# projet_pcb_naked_g431.net
KiCad netlist of a schematic drawn in Altium Designer
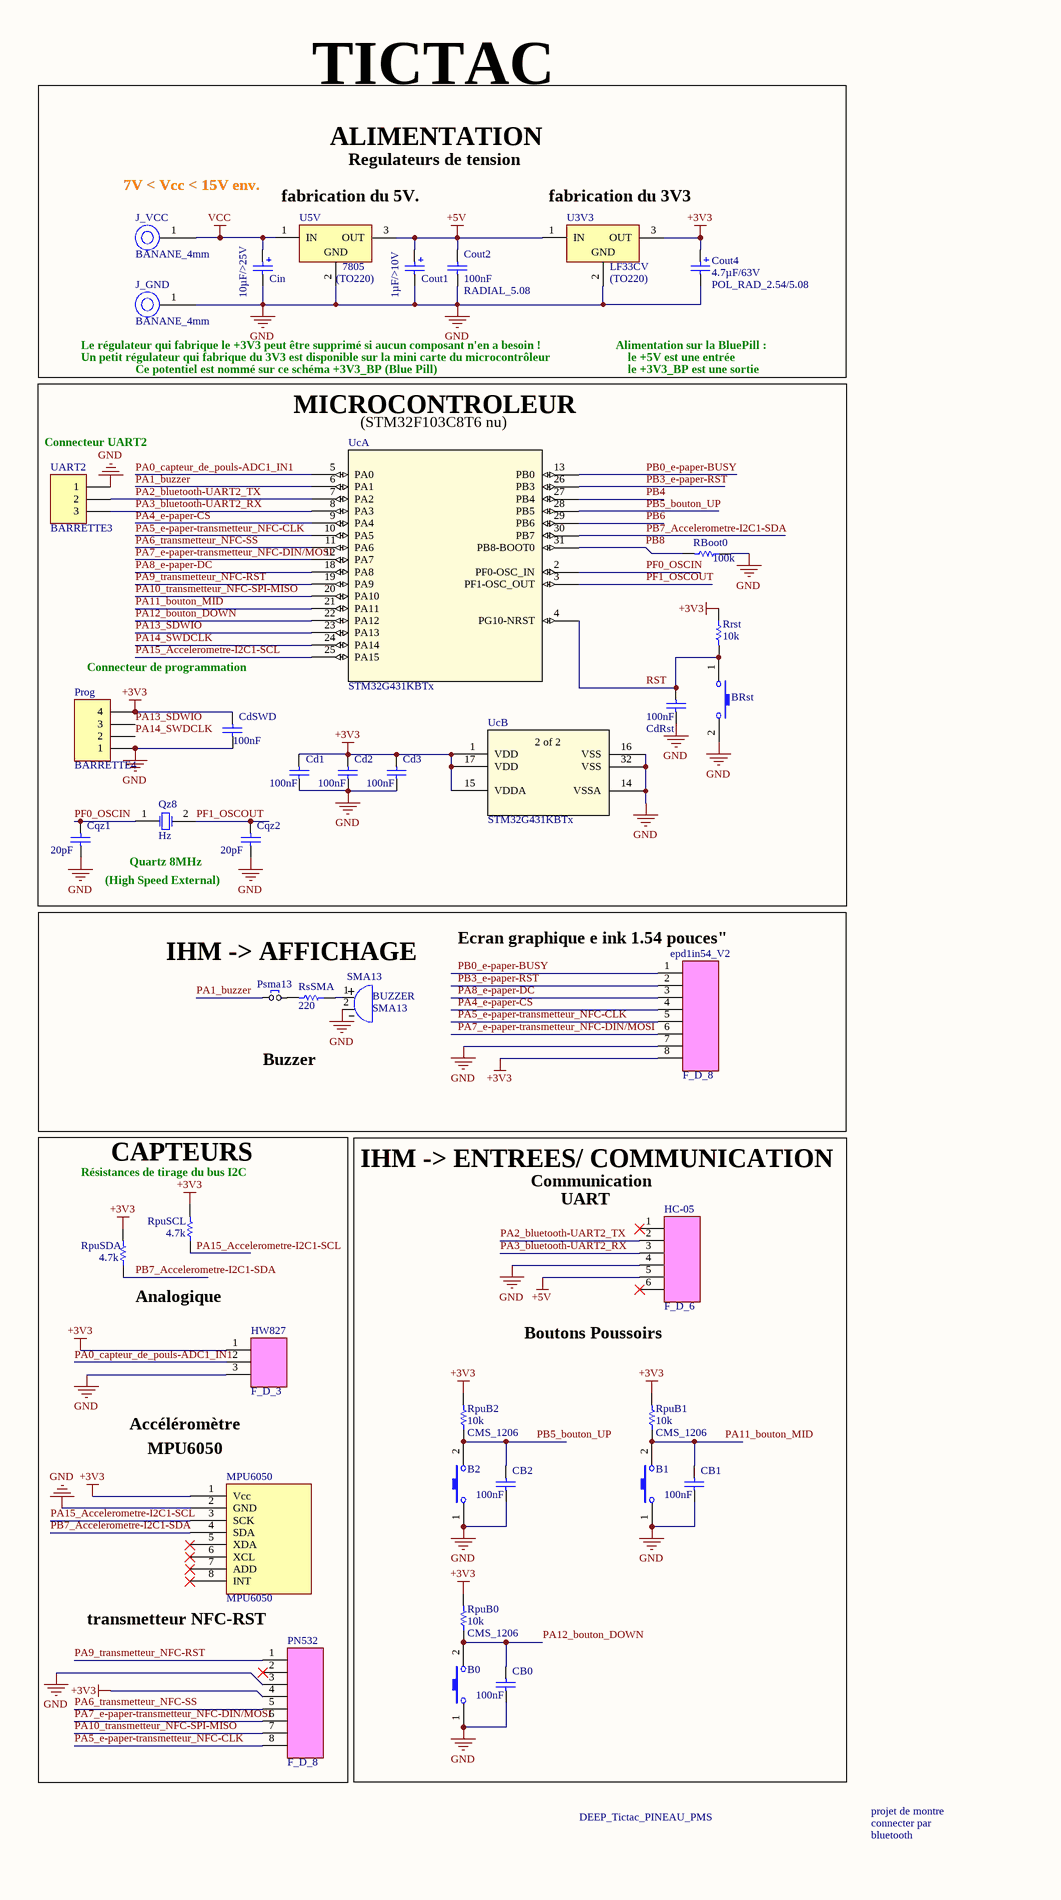
[diagram p0: projet_pcb_naked_g431.SchDoc, left]
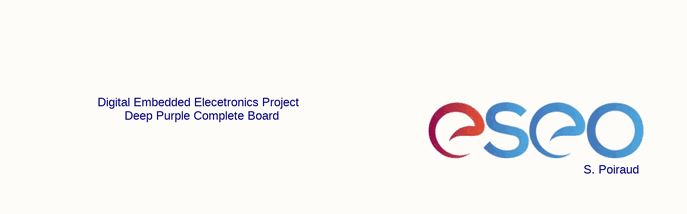
[diagram p1: projet_pcb_naked_g431.SchDoc, right]

(export (version "E")
  (design (tool "Eeschema 10.0.6"))
  (components
    (comp (ref "B0")
      (value "BOUTON_POUSSOIR_MINIATURE_TRAVERSANT")
      (footprint "BOUTON_POUSSE_PLAT_6x6")
      (description "BOUTON POUSSOIR MINIATURE TRAVERSANT ON/OFF")
      (libsource (lib "commutation") (part "BOUTON_POUSSOIR_MINIATURE_TRAVERSANT"))
    )
    (comp (ref "B1")
      (value "BOUTON_POUSSOIR_MINIATURE_TRAVERSANT")
      (footprint "BOUTON_POUSSE_PLAT_6x6")
      (description "BOUTON POUSSOIR MINIATURE TRAVERSANT ON/OFF")
      (libsource (lib "commutation") (part "BOUTON_POUSSOIR_MINIATURE_TRAVERSANT"))
    )
    (comp (ref "B2")
      (value "BOUTON_POUSSOIR_MINIATURE_TRAVERSANT")
      (footprint "BOUTON_POUSSE_PLAT_6x6")
      (description "BOUTON POUSSOIR MINIATURE TRAVERSANT ON/OFF")
      (libsource (lib "commutation") (part "BOUTON_POUSSOIR_MINIATURE_TRAVERSANT"))
    )
    (comp (ref "BRst")
      (value "BOUTON_POUSSOIR_MINIATURE_TRAVERSANT")
      (footprint "BOUTON_POUSSE_PLAT_6x6")
      (description "BOUTON POUSSOIR MINIATURE TRAVERSANT ON/OFF")
      (libsource (lib "commutation") (part "BOUTON_POUSSOIR_MINIATURE_TRAVERSANT"))
    )
    (comp (ref "CB0")
      (value "100nF")
      (footprint "C0805_N")
      (fields (field (name "Comment") "Condensateur 0805"))
      (libsource (lib "composants passifs") (part "CONDENSATEUR_CER_RAD_5.08"))
    )
    (comp (ref "CB1")
      (value "100nF")
      (footprint "C0805_N")
      (fields (field (name "Comment") "Condensateur 0805"))
      (libsource (lib "composants passifs") (part "CONDENSATEUR_CER_RAD_5.08"))
    )
    (comp (ref "CB2")
      (value "100nF")
      (footprint "C0805_N")
      (fields (field (name "Comment") "Condensateur 0805"))
      (libsource (lib "composants passifs") (part "CONDENSATEUR_CER_RAD_5.08"))
    )
    (comp (ref "Cd1")
      (value "100nF")
      (footprint "C0805_N")
      (fields (field (name "Comment") "Condensateur 0805"))
      (libsource (lib "composants passifs") (part "CONDENSATEUR_CER_RAD_5.08"))
    )
    (comp (ref "Cd2")
      (value "100nF")
      (footprint "C0805_N")
      (fields (field (name "Comment") "Condensateur 0805"))
      (libsource (lib "composants passifs") (part "CONDENSATEUR_CER_RAD_5.08"))
    )
    (comp (ref "Cd3")
      (value "100nF")
      (footprint "C0805_N")
      (fields (field (name "Comment") "Condensateur 0805"))
      (libsource (lib "composants passifs") (part "CONDENSATEUR_CER_RAD_5.08"))
    )
    (comp (ref "CdRst")
      (value "100nF")
      (footprint "C0805_N")
      (fields (field (name "Comment") "Condensateur 0805"))
      (libsource (lib "composants passifs") (part "CONDENSATEUR_CER_RAD_5.08"))
    )
    (comp (ref "CdSWD")
      (value "100nF")
      (footprint "C0805_N")
      (fields (field (name "Comment") "Condensateur 0805"))
      (libsource (lib "composants passifs") (part "CONDENSATEUR_CER_RAD_5.08"))
    )
    (comp (ref "Cin")
      (value "10µF/>25V")
      (footprint "CONDENSATEUR_POLARISE_ELECTROLYTIQUE_RADIAL_2.0/5.08")
      (description "CONDENSATEUR POLARISE ELECTROLYTIQUE RADIAL 2.0/5.08")
      (fields (field (name "Comment") "CONDENSATEUR_POL_ELECTROLY_RAD_2.0/5.08"))
      (libsource (lib "composants passifs") (part "CONDENSATEUR_POL_ELECTROLY_RAD_2.0/5.08"))
    )
    (comp (ref "Cout1")
      (value "1µF/>10V")
      (footprint "CONDENSATEUR_POLARISE_ELECTROLYTIQUE_RADIAL_2.0/5.08")
      (description "CONDENSATEUR POLARISE ELECTROLYTIQUE RADIAL 2.0/5.08")
      (fields (field (name "Comment") "CONDENSATEUR_POL_ELECTROLY_RAD_2.0/5.08"))
      (libsource (lib "composants passifs") (part "CONDENSATEUR_POL_ELECTROLY_RAD_2.0/5.08"))
    )
    (comp (ref "Cout2")
      (value "100nF")
      (footprint "CONDENSATEUR_CERAMIQUE_RADIAL_5.08")
      (description "CONDENSATEUR TRAVERSANT CERAMIQUE RADIAL 5.08mm")
      (fields (field (name "TYPE") "RADIAL_5.08") (field (name "Comment") "CONDENSATEUR_CER_RAD_5.08"))
      (libsource (lib "composants passifs") (part "CONDENSATEUR_CER_RAD_5.08"))
    )
    (comp (ref "Cout4")
      (value "4.7µF/63V")
      (footprint "CONDENSATEUR_POLARISE_ELECTROLYTIQUE_RADIAL_2.54/5.08")
      (description "CONDENSATEUR POLARISE ELECTROLYTIQUE RADIAL 2.54/5.08")
      (fields
        (field (name "TYPE") "POL_RAD_2.54/5.08")
        (field (name "Comment") "CONDENSATEUR_POL_ELECTROLY_RAD_2.54/5.08")
      )
      (libsource (lib "composants passifs") (part "CONDENSATEUR_POL_ELECTROLY_RAD_2.54/5.08"))
    )
    (comp (ref "Cqz1")
      (value "20pF")
      (footprint "C0805_N")
      (fields (field (name "Comment") "Condensateur 0805"))
      (libsource (lib "composants passifs") (part "CONDENSATEUR_CER_RAD_5.08"))
    )
    (comp (ref "Cqz2")
      (value "20pF")
      (footprint "C0805_N")
      (fields (field (name "Comment") "Condensateur 0805"))
      (libsource (lib "composants passifs") (part "CONDENSATEUR_CER_RAD_5.08"))
    )
    (comp (ref "epd1in54_V2")
      (value "BARRETTE_8 CONTACTS_1 RANGEE_FEMELLE_DROITE")
      (footprint "BARRETTE_8_F_D")
      (fields (field (name "TYPE") "F_D_8"))
      (libsource (lib "connecteurs") (part "BARRETTE_8 CONTACTS_1 RANGEE_FEMELLE_DROITE"))
    )
    (comp (ref "HC-05")
      (value "BARRETTE_6 CONTACTS_1 RANGEE_FEMELLE_DROITE")
      (footprint "BARRETTE_6_F_D")
      (description "BARRETTE 6 CONTACTS 1 RANGEE FEMELLE DROITE")
      (fields (field (name "TYPE") "F_D_6"))
      (libsource (lib "connecteurs") (part "BARRETTE_6 CONTACTS_1 RANGEE_FEMELLE_DROITE"))
    )
    (comp (ref "HW827")
      (value "BARRETTE 3 CONTACTS 1 RANGEE FEMELLE DROITE")
      (footprint "BARRETTE_3_F_D")
      (fields (field (name "TYPE") "F_D_3"))
      (libsource (lib "connecteurs") (part "BARRETTE_3 CONTACTS_1 RANGEE_FEMELLE_DROITE"))
    )
    (comp (ref "J_GND")
      (value "DOUILLE BANANE 4mm")
      (footprint "DOUILLE_BANANE_4mm")
      (description "DOUILLE BANANE 4 mm")
      (fields (field (name "TYPE") "BANANE_4mm"))
      (libsource (lib "connecteurs") (part "DOUILLE_BANANE_4mm"))
    )
    (comp (ref "J_VCC")
      (value "DOUILLE BANANE 4mm")
      (footprint "DOUILLE_BANANE_4mm")
      (description "DOUILLE BANANE 4 mm")
      (fields (field (name "TYPE") "BANANE_4mm"))
      (libsource (lib "connecteurs") (part "DOUILLE_BANANE_4mm"))
    )
    (comp (ref "MPU6050") (value "MPU6050") (footprint "MPU6050") (libsource (lib "DEEP") (part "MPU6050")))
    (comp (ref "PN532")
      (value "BARRETTE_8 CONTACTS_1 RANGEE_FEMELLE_DROITE")
      (footprint "BARRETTE_8_F_D")
      (fields (field (name "TYPE") "F_D_8"))
      (libsource (lib "connecteurs") (part "BARRETTE_8 CONTACTS_1 RANGEE_FEMELLE_DROITE"))
    )
    (comp (ref "Prog")
      (value "BARRETTE4")
      (footprint "HE14_4")
      (description "Header, 4-Pin")
      (fields (field (name "PUBLISHER") "Altium Limited"))
      (libsource (lib "Connecteur") (part "BARRETTE4"))
    )
    (comp (ref "Psma13")
      (value "Jumper SIP 2.54")
      (footprint "HDR1X2")
      (description "Jumper SIP2.54")
      (libsource (lib "Connecteur") (part "Jumper SIP2.54"))
    )
    (comp (ref "Qz8")
      (value "Hz")
      (footprint "HC49/4H_SMX")
      (description "Crystal Oscillator")
      (fields (field (name "PUBLISHER") "Altium Limited"))
      (libsource (lib "_ROBOT") (part "Quartz"))
    )
    (comp (ref "RBoot0")
      (value "100k")
      (footprint "R1206_N")
      (description "Resistor")
      (fields (field (name "PUBLISHER") "Altium Limited"))
      (libsource (lib "_ROBOT") (part "Resistor"))
    )
    (comp (ref "RpuB0")
      (value "10k")
      (footprint "RESISTANCE_CMS_1206")
      (description "RESISTANCE CMS 1206")
      (fields (field (name "TYPE") "CMS_1206") (field (name "Comment") "RESISTANCE_CMS_1206"))
      (libsource (lib "composants passifs") (part "RESISTANCE_CMS_1206"))
    )
    (comp (ref "RpuB1")
      (value "10k")
      (footprint "RESISTANCE_CMS_1206")
      (description "RESISTANCE CMS 1206")
      (fields (field (name "TYPE") "CMS_1206") (field (name "Comment") "RESISTANCE_CMS_1206"))
      (libsource (lib "composants passifs") (part "RESISTANCE_CMS_1206"))
    )
    (comp (ref "RpuB2")
      (value "10k")
      (footprint "RESISTANCE_CMS_1206")
      (description "RESISTANCE CMS 1206")
      (fields (field (name "TYPE") "CMS_1206") (field (name "Comment") "RESISTANCE_CMS_1206"))
      (libsource (lib "composants passifs") (part "RESISTANCE_CMS_1206"))
    )
    (comp (ref "RpuSCL")
      (value "4.7k")
      (footprint "R1206_N")
      (description "Resistor")
      (fields (field (name "PUBLISHER") "Altium Limited"))
      (libsource (lib "_ROBOT") (part "Resistor"))
    )
    (comp (ref "RpuSDA")
      (value "4.7k")
      (footprint "R1206_N")
      (description "Resistor")
      (fields (field (name "PUBLISHER") "Altium Limited"))
      (libsource (lib "_ROBOT") (part "Resistor"))
    )
    (comp (ref "Rrst")
      (value "10k")
      (footprint "R1206_N")
      (description "Resistor")
      (fields (field (name "PUBLISHER") "Altium Limited"))
      (libsource (lib "_ROBOT") (part "Resistor"))
    )
    (comp (ref "RsSMA")
      (value "220")
      (footprint "R1206_N")
      (description "Resistor")
      (fields (field (name "PUBLISHER") "Altium Limited"))
      (libsource (lib "_ROBOT") (part "Resistor"))
    )
    (comp (ref "SMA13")
      (value "SMA13")
      (footprint "BUZZER_SMA13")
      (description "BUZZER SMA13")
      (fields (field (name "TYPE") "BUZZER") (field (name "Comment") "BUZZER_SMA13"))
      (libsource (lib "electromecanique") (part "BUZZER_SMA13"))
    )
    (comp (ref "U3V3")
      (value "REGULATEUR_TO220_78XX")
      (footprint "REGULATEUR_TO220_78XX")
      (description "REGULATEUR DE TENSION POSITIVE 78XX BOITIER TO220")
      (fields (field (name "TYPE") "LF33CV") (field (name "PACKAGE") "(TO220)"))
      (libsource (lib "composants actifs") (part "REGULATEUR_TO220_78XX"))
    )
    (comp (ref "U5V")
      (value "REGULATEUR_TO220_78XX")
      (footprint "REGULATEUR_TO220_78XX")
      (description "REGULATEUR DE TENSION POSITIVE 78XX BOITIER TO220")
      (fields (field (name "TYPE") "7805") (field (name "PACKAGE") "(TO220)"))
      (libsource (lib "composants actifs") (part "REGULATEUR_TO220_78XX"))
    )
    (comp (ref "UART2")
      (value "BARRETTE3")
      (footprint "HDR1X3")
      (description "Header, 3-Pin")
      (fields (field (name "PUBLISHER") "Altium Limited"))
      (libsource (lib "Connecteur") (part "BARRETTE3"))
    )
    (comp (ref "Uc")
      (value "STM32G431KBTx")
      (footprint "LQFP-32")
      (fields
        (field (name "MANUFACTURER_PART_NUMBER") "stm32g4_lqfp32_t1")
        (field (name "COPYRIGHT") "Copyright (C) 2016 Accelerated Designs. All rights reserved")
      )
      (libsource (lib "ST Microelectronics STM32 G4") (part "STM32G431KBTx"))
    )
  )
  (nets
    (net (code "1") (name "+3V3") (class "Default")
      (node (ref "Cd1") (pin "2") (pinfunction "2_2") (pintype "passive"))
      (node (ref "Cd2") (pin "2") (pinfunction "2_2") (pintype "passive"))
      (node (ref "Cd3") (pin "2") (pinfunction "2_2") (pintype "passive"))
      (node (ref "CdSWD") (pin "2") (pinfunction "2_2") (pintype "passive"))
      (node (ref "Cout4") (pin "1") (pinfunction "1_1") (pintype "passive"))
      (node (ref "HW827") (pin "1") (pinfunction "1_1") (pintype "passive"))
      (node (ref "MPU6050") (pin "1") (pinfunction "Vcc_1") (pintype "passive"))
      (node (ref "PN532") (pin "4") (pinfunction "4_4") (pintype "passive"))
      (node (ref "Prog") (pin "4") (pinfunction "4_4") (pintype "passive"))
      (node (ref "RpuB0") (pin "2") (pinfunction "2_2") (pintype "passive"))
      (node (ref "RpuB1") (pin "2") (pinfunction "2_2") (pintype "passive"))
      (node (ref "RpuB2") (pin "2") (pinfunction "2_2") (pintype "passive"))
      (node (ref "RpuSCL") (pin "2") (pinfunction "2_2") (pintype "passive"))
      (node (ref "RpuSDA") (pin "2") (pinfunction "2_2") (pintype "passive"))
      (node (ref "Rrst") (pin "1") (pinfunction "1_1") (pintype "passive"))
      (node (ref "U3V3") (pin "3") (pinfunction "OUT_3") (pintype "power_in"))
      (node (ref "Uc") (pin "1") (pinfunction "VDD_1") (pintype "power_in"))
      (node (ref "Uc") (pin "15") (pinfunction "VDDA_15") (pintype "power_in"))
      (node (ref "Uc") (pin "17") (pinfunction "VDD_17") (pintype "power_in"))
      (node (ref "epd1in54_V2") (pin "8") (pinfunction "8_8") (pintype "passive"))
    )
    (net (code "2") (name "+5V") (class "Default")
      (node (ref "Cout1") (pin "1") (pinfunction "1_1") (pintype "passive"))
      (node (ref "Cout2") (pin "2") (pinfunction "2_2") (pintype "passive"))
      (node (ref "HC-05") (pin "5") (pinfunction "5_5") (pintype "passive"))
      (node (ref "U3V3") (pin "1") (pinfunction "IN_1") (pintype "power_in"))
      (node (ref "U5V") (pin "3") (pinfunction "OUT_3") (pintype "power_in"))
    )
    (net (code "3") (name "/PA0_capteur_de_pouls-ADC1_IN1") (class "Default")
      (node (ref "HW827") (pin "2") (pinfunction "2_2") (pintype "passive"))
      (node (ref "Uc") (pin "5") (pinfunction "PA0_5") (pintype "bidirectional"))
    )
    (net (code "4") (name "/PA1_buzzer") (class "Default")
      (node (ref "Psma13") (pin "1") (pinfunction "1_1") (pintype "passive"))
      (node (ref "Uc") (pin "6") (pinfunction "PA1_6") (pintype "bidirectional"))
    )
    (net (code "5") (name "/PA2_bluetooth-UART2_TX") (class "Default")
      (node (ref "HC-05") (pin "2") (pinfunction "2_2") (pintype "passive"))
      (node (ref "UART2") (pin "2") (pinfunction "2_2") (pintype "passive"))
      (node (ref "Uc") (pin "7") (pinfunction "PA2_7") (pintype "bidirectional"))
    )
    (net (code "6") (name "/PA3_bluetooth-UART2_RX") (class "Default")
      (node (ref "HC-05") (pin "3") (pinfunction "3_3") (pintype "passive"))
      (node (ref "UART2") (pin "3") (pinfunction "3_3") (pintype "passive"))
      (node (ref "Uc") (pin "8") (pinfunction "PA3_8") (pintype "bidirectional"))
    )
    (net (code "7") (name "/PA4_e-paper-CS") (class "Default")
      (node (ref "Uc") (pin "9") (pinfunction "PA4_9") (pintype "bidirectional"))
      (node (ref "epd1in54_V2") (pin "4") (pinfunction "4_4") (pintype "passive"))
    )
    (net (code "8") (name "/PA5_e-paper-transmetteur_NFC-CLK") (class "Default")
      (node (ref "PN532") (pin "8") (pinfunction "8_8") (pintype "passive"))
      (node (ref "Uc") (pin "10") (pinfunction "PA5_10") (pintype "bidirectional"))
      (node (ref "epd1in54_V2") (pin "5") (pinfunction "5_5") (pintype "passive"))
    )
    (net (code "9") (name "/PA6_transmetteur_NFC-SS") (class "Default")
      (node (ref "PN532") (pin "5") (pinfunction "5_5") (pintype "passive"))
      (node (ref "Uc") (pin "11") (pinfunction "PA6_11") (pintype "bidirectional"))
    )
    (net (code "10") (name "/PA7_e-paper-transmetteur_NFC-DIN{slash}MOSI") (class "Default")
      (node (ref "PN532") (pin "6") (pinfunction "6_6") (pintype "passive"))
      (node (ref "Uc") (pin "12") (pinfunction "PA7_12") (pintype "bidirectional"))
      (node (ref "epd1in54_V2") (pin "6") (pinfunction "6_6") (pintype "passive"))
    )
    (net (code "11") (name "/PA8_e-paper-DC") (class "Default")
      (node (ref "Uc") (pin "18") (pinfunction "PA8_18") (pintype "bidirectional"))
      (node (ref "epd1in54_V2") (pin "3") (pinfunction "3_3") (pintype "passive"))
    )
    (net (code "12") (name "/PA9_transmetteur_NFC-RST") (class "Default")
      (node (ref "PN532") (pin "1") (pinfunction "1_1") (pintype "passive"))
      (node (ref "Uc") (pin "19") (pinfunction "PA9_19") (pintype "bidirectional"))
    )
    (net (code "13") (name "/PA10_transmetteur_NFC-SPI-MISO") (class "Default")
      (node (ref "PN532") (pin "7") (pinfunction "7_7") (pintype "passive"))
      (node (ref "Uc") (pin "20") (pinfunction "PA10_20") (pintype "bidirectional"))
    )
    (net (code "14") (name "/PA11_bouton_MID") (class "Default")
      (node (ref "B1") (pin "2") (pinfunction "2_2") (pintype "passive"))
      (node (ref "CB1") (pin "2") (pinfunction "2_2") (pintype "passive"))
      (node (ref "RpuB1") (pin "1") (pinfunction "1_1") (pintype "passive"))
      (node (ref "Uc") (pin "21") (pinfunction "PA11_21") (pintype "bidirectional"))
    )
    (net (code "15") (name "/PA12_bouton_DOWN") (class "Default")
      (node (ref "B0") (pin "2") (pinfunction "2_2") (pintype "passive"))
      (node (ref "CB0") (pin "2") (pinfunction "2_2") (pintype "passive"))
      (node (ref "RpuB0") (pin "1") (pinfunction "1_1") (pintype "passive"))
      (node (ref "Uc") (pin "22") (pinfunction "PA12_22") (pintype "bidirectional"))
    )
    (net (code "16") (name "/PA13_SDWIO") (class "Default")
      (node (ref "Prog") (pin "3") (pinfunction "3_3") (pintype "passive"))
      (node (ref "Uc") (pin "23") (pinfunction "PA13_23") (pintype "bidirectional"))
    )
    (net (code "17") (name "/PA14_SWDCLK") (class "Default")
      (node (ref "Prog") (pin "2") (pinfunction "2_2") (pintype "passive"))
      (node (ref "Uc") (pin "24") (pinfunction "PA14_24") (pintype "bidirectional"))
    )
    (net (code "18") (name "/PA15_Accelerometre-I2C1-SCL") (class "Default")
      (node (ref "MPU6050") (pin "3") (pinfunction "SCK_3") (pintype "passive"))
      (node (ref "RpuSCL") (pin "1") (pinfunction "1_1") (pintype "passive"))
      (node (ref "Uc") (pin "25") (pinfunction "PA15_25") (pintype "bidirectional"))
    )
    (net (code "19") (name "/PB0_e-paper-BUSY") (class "Default")
      (node (ref "Uc") (pin "13") (pinfunction "PB0_13") (pintype "bidirectional"))
      (node (ref "epd1in54_V2") (pin "1") (pinfunction "1_1") (pintype "passive"))
    )
    (net (code "20") (name "/PB3_e-paper-RST") (class "Default")
      (node (ref "Uc") (pin "26") (pinfunction "PB3_26") (pintype "bidirectional"))
      (node (ref "epd1in54_V2") (pin "2") (pinfunction "2_2") (pintype "passive"))
    )
    (net (code "21") (name "/PB4") (class "Default")
      (node (ref "Uc") (pin "27") (pinfunction "PB4_27") (pintype "bidirectional"))
    )
    (net (code "22") (name "/PB5_bouton_UP") (class "Default")
      (node (ref "B2") (pin "2") (pinfunction "2_2") (pintype "passive"))
      (node (ref "CB2") (pin "2") (pinfunction "2_2") (pintype "passive"))
      (node (ref "RpuB2") (pin "1") (pinfunction "1_1") (pintype "passive"))
      (node (ref "Uc") (pin "28") (pinfunction "PB5_28") (pintype "bidirectional"))
    )
    (net (code "23") (name "/PB6") (class "Default")
      (node (ref "Uc") (pin "29") (pinfunction "PB6_29") (pintype "bidirectional"))
    )
    (net (code "24") (name "/PB7_Accelerometre-I2C1-SDA") (class "Default")
      (node (ref "MPU6050") (pin "4") (pinfunction "SDA_4") (pintype "passive"))
      (node (ref "RpuSDA") (pin "1") (pinfunction "1_1") (pintype "passive"))
      (node (ref "Uc") (pin "30") (pinfunction "PB7_30") (pintype "bidirectional"))
    )
    (net (code "25") (name "/PB8") (class "Default")
      (node (ref "RBoot0") (pin "2") (pinfunction "2_2") (pintype "passive"))
      (node (ref "Uc") (pin "31") (pinfunction "PB8-BOOT0_31") (pintype "bidirectional"))
    )
    (net (code "26") (name "/PF0_OSCIN") (class "Default")
      (node (ref "Cqz1") (pin "2") (pinfunction "2_2") (pintype "passive"))
      (node (ref "Qz8") (pin "1") (pinfunction "OSC1_1") (pintype "passive"))
      (node (ref "Uc") (pin "2") (pinfunction "PF0-OSC_IN_2") (pintype "bidirectional"))
    )
    (net (code "27") (name "/PF1_OSCOUT") (class "Default")
      (node (ref "Cqz2") (pin "2") (pinfunction "2_2") (pintype "passive"))
      (node (ref "Qz8") (pin "2") (pinfunction "OSC2_2") (pintype "passive"))
      (node (ref "Uc") (pin "3") (pinfunction "PF1-OSC_OUT_3") (pintype "bidirectional"))
    )
    (net (code "28") (name "/RST") (class "Default")
      (node (ref "BRst") (pin "1") (pinfunction "1_1") (pintype "passive"))
      (node (ref "CdRst") (pin "2") (pinfunction "2_2") (pintype "passive"))
      (node (ref "Rrst") (pin "2") (pinfunction "2_2") (pintype "passive"))
      (node (ref "Uc") (pin "4") (pinfunction "PG10-NRST_4") (pintype "bidirectional"))
    )
    (net (code "29") (name "GND") (class "Default")
      (node (ref "B0") (pin "1") (pinfunction "1_1") (pintype "passive"))
      (node (ref "B1") (pin "1") (pinfunction "1_1") (pintype "passive"))
      (node (ref "B2") (pin "1") (pinfunction "1_1") (pintype "passive"))
      (node (ref "BRst") (pin "2") (pinfunction "2_2") (pintype "passive"))
      (node (ref "CB0") (pin "1") (pinfunction "1_1") (pintype "passive"))
      (node (ref "CB1") (pin "1") (pinfunction "1_1") (pintype "passive"))
      (node (ref "CB2") (pin "1") (pinfunction "1_1") (pintype "passive"))
      (node (ref "Cd1") (pin "1") (pinfunction "1_1") (pintype "passive"))
      (node (ref "Cd2") (pin "1") (pinfunction "1_1") (pintype "passive"))
      (node (ref "Cd3") (pin "1") (pinfunction "1_1") (pintype "passive"))
      (node (ref "CdRst") (pin "1") (pinfunction "1_1") (pintype "passive"))
      (node (ref "CdSWD") (pin "1") (pinfunction "1_1") (pintype "passive"))
      (node (ref "Cin") (pin "2") (pinfunction "2_2") (pintype "passive"))
      (node (ref "Cout1") (pin "2") (pinfunction "2_2") (pintype "passive"))
      (node (ref "Cout2") (pin "1") (pinfunction "1_1") (pintype "passive"))
      (node (ref "Cout4") (pin "2") (pinfunction "2_2") (pintype "passive"))
      (node (ref "Cqz1") (pin "1") (pinfunction "1_1") (pintype "passive"))
      (node (ref "Cqz2") (pin "1") (pinfunction "1_1") (pintype "passive"))
      (node (ref "HC-05") (pin "4") (pinfunction "4_4") (pintype "passive"))
      (node (ref "HW827") (pin "3") (pinfunction "3_3") (pintype "passive"))
      (node (ref "J_GND") (pin "1") (pinfunction "1_1") (pintype "passive"))
      (node (ref "MPU6050") (pin "2") (pinfunction "GND_2") (pintype "passive"))
      (node (ref "PN532") (pin "3") (pinfunction "3_3") (pintype "passive"))
      (node (ref "Prog") (pin "1") (pinfunction "1_1") (pintype "passive"))
      (node (ref "RBoot0") (pin "1") (pinfunction "1_1") (pintype "passive"))
      (node (ref "SMA13") (pin "2") (pinfunction "2_2") (pintype "passive"))
      (node (ref "U3V3") (pin "2") (pinfunction "GND_2") (pintype "power_in"))
      (node (ref "U5V") (pin "2") (pinfunction "GND_2") (pintype "power_in"))
      (node (ref "UART2") (pin "1") (pinfunction "1_1") (pintype "passive"))
      (node (ref "Uc") (pin "14") (pinfunction "VSSA_14") (pintype "power_in"))
      (node (ref "Uc") (pin "16") (pinfunction "VSS_16") (pintype "power_in"))
      (node (ref "Uc") (pin "32") (pinfunction "VSS_32") (pintype "power_in"))
      (node (ref "epd1in54_V2") (pin "7") (pinfunction "7_7") (pintype "passive"))
    )
    (net (code "30") (name "Net-(Psma13-Pad2)") (class "Default")
      (node (ref "Psma13") (pin "2") (pinfunction "2_2") (pintype "passive"))
      (node (ref "RsSMA") (pin "2") (pinfunction "2_2") (pintype "passive"))
    )
    (net (code "31") (name "Net-(RsSMA-Pad1)") (class "Default")
      (node (ref "RsSMA") (pin "1") (pinfunction "1_1") (pintype "passive"))
      (node (ref "SMA13") (pin "1") (pinfunction "1_1") (pintype "passive"))
    )
    (net (code "32") (name "VCC") (class "Default")
      (node (ref "Cin") (pin "1") (pinfunction "1_1") (pintype "passive"))
      (node (ref "J_VCC") (pin "1") (pinfunction "1_1") (pintype "passive"))
      (node (ref "U5V") (pin "1") (pinfunction "IN_1") (pintype "power_in"))
    )
    (net (code "33") (name "unconnected-(HC-05-Pad1)") (class "Default")
      (node (ref "HC-05") (pin "1") (pinfunction "1_1") (pintype "passive+no_connect"))
    )
    (net (code "34") (name "unconnected-(HC-05-Pad6)") (class "Default")
      (node (ref "HC-05") (pin "6") (pinfunction "6_6") (pintype "passive+no_connect"))
    )
    (net (code "35") (name "unconnected-(MPU6050-ADD-Pad7)") (class "Default")
      (node (ref "MPU6050") (pin "7") (pinfunction "ADD_7") (pintype "passive+no_connect"))
    )
    (net (code "36") (name "unconnected-(MPU6050-INT-Pad8)") (class "Default")
      (node (ref "MPU6050") (pin "8") (pinfunction "INT_8") (pintype "passive+no_connect"))
    )
    (net (code "37") (name "unconnected-(MPU6050-XCL-Pad6)") (class "Default")
      (node (ref "MPU6050") (pin "6") (pinfunction "XCL_6") (pintype "passive+no_connect"))
    )
    (net (code "38") (name "unconnected-(MPU6050-XDA-Pad5)") (class "Default")
      (node (ref "MPU6050") (pin "5") (pinfunction "XDA_5") (pintype "passive+no_connect"))
    )
    (net (code "39") (name "unconnected-(PN532-Pad2)") (class "Default")
      (node (ref "PN532") (pin "2") (pinfunction "2_2") (pintype "passive+no_connect"))
    )
  )
)
